# V2.net
KiCad netlist of a schematic drawn in Altium Designer
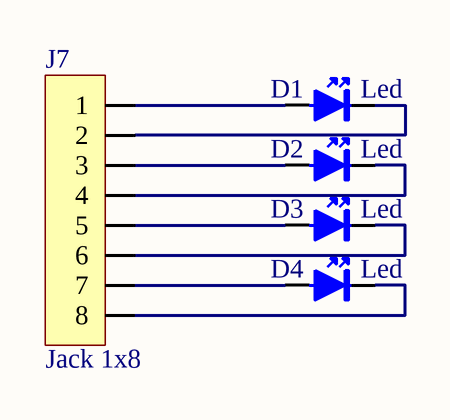
[diagram p0: 海关全向电源指示灯板V2.SchDoc]

(export (version "E")
  (design (tool "Eeschema 10.0.6"))
  (components
    (comp (ref "D1")
      (value "Led")
      (footprint "Led-D3")
      (description "light emitted diode")
      (libsource (lib "RLCYDF") (part "Led"))
    )
    (comp (ref "D2")
      (value "Led")
      (footprint "Led-D3")
      (description "light emitted diode")
      (libsource (lib "RLCYDF") (part "Led"))
    )
    (comp (ref "D3")
      (value "Led")
      (footprint "Led-D3")
      (description "light emitted diode")
      (libsource (lib "RLCYDF") (part "Led"))
    )
    (comp (ref "D4")
      (value "Led")
      (footprint "Led-D3")
      (description "light emitted diode")
      (libsource (lib "RLCYDF") (part "Led"))
    )
    (comp (ref "J7")
      (value "Jack 1x8")
      (footprint "ZH-8AWD")
      (description "插座")
      (libsource (lib "Connector") (part "Jack 1x8"))
    )
  )
  (nets
    (net (code "1") (name "Net-(D1-A)") (class "Default")
      (node (ref "D1") (pin "1") (pinfunction "A_1") (pintype "passive"))
      (node (ref "J7") (pin "1") (pinfunction "1_1") (pintype "passive"))
    )
    (net (code "2") (name "Net-(D1-K)") (class "Default")
      (node (ref "D1") (pin "2") (pinfunction "K_2") (pintype "passive"))
      (node (ref "J7") (pin "2") (pinfunction "2_2") (pintype "passive"))
    )
    (net (code "3") (name "Net-(D2-A)") (class "Default")
      (node (ref "D2") (pin "1") (pinfunction "A_1") (pintype "passive"))
      (node (ref "J7") (pin "3") (pinfunction "3_3") (pintype "passive"))
    )
    (net (code "4") (name "Net-(D2-K)") (class "Default")
      (node (ref "D2") (pin "2") (pinfunction "K_2") (pintype "passive"))
      (node (ref "J7") (pin "4") (pinfunction "4_4") (pintype "passive"))
    )
    (net (code "5") (name "Net-(D3-A)") (class "Default")
      (node (ref "D3") (pin "1") (pinfunction "A_1") (pintype "passive"))
      (node (ref "J7") (pin "5") (pinfunction "5_5") (pintype "passive"))
    )
    (net (code "6") (name "Net-(D3-K)") (class "Default")
      (node (ref "D3") (pin "2") (pinfunction "K_2") (pintype "passive"))
      (node (ref "J7") (pin "6") (pinfunction "6_6") (pintype "passive"))
    )
    (net (code "7") (name "Net-(D4-A)") (class "Default")
      (node (ref "D4") (pin "1") (pinfunction "A_1") (pintype "passive"))
      (node (ref "J7") (pin "7") (pinfunction "7_7") (pintype "passive"))
    )
    (net (code "8") (name "Net-(D4-K)") (class "Default")
      (node (ref "D4") (pin "2") (pinfunction "K_2") (pintype "passive"))
      (node (ref "J7") (pin "8") (pinfunction "8_8") (pintype "passive"))
    )
  )
)
